# ABC.net
KiCad netlist of a schematic drawn in EAGLE
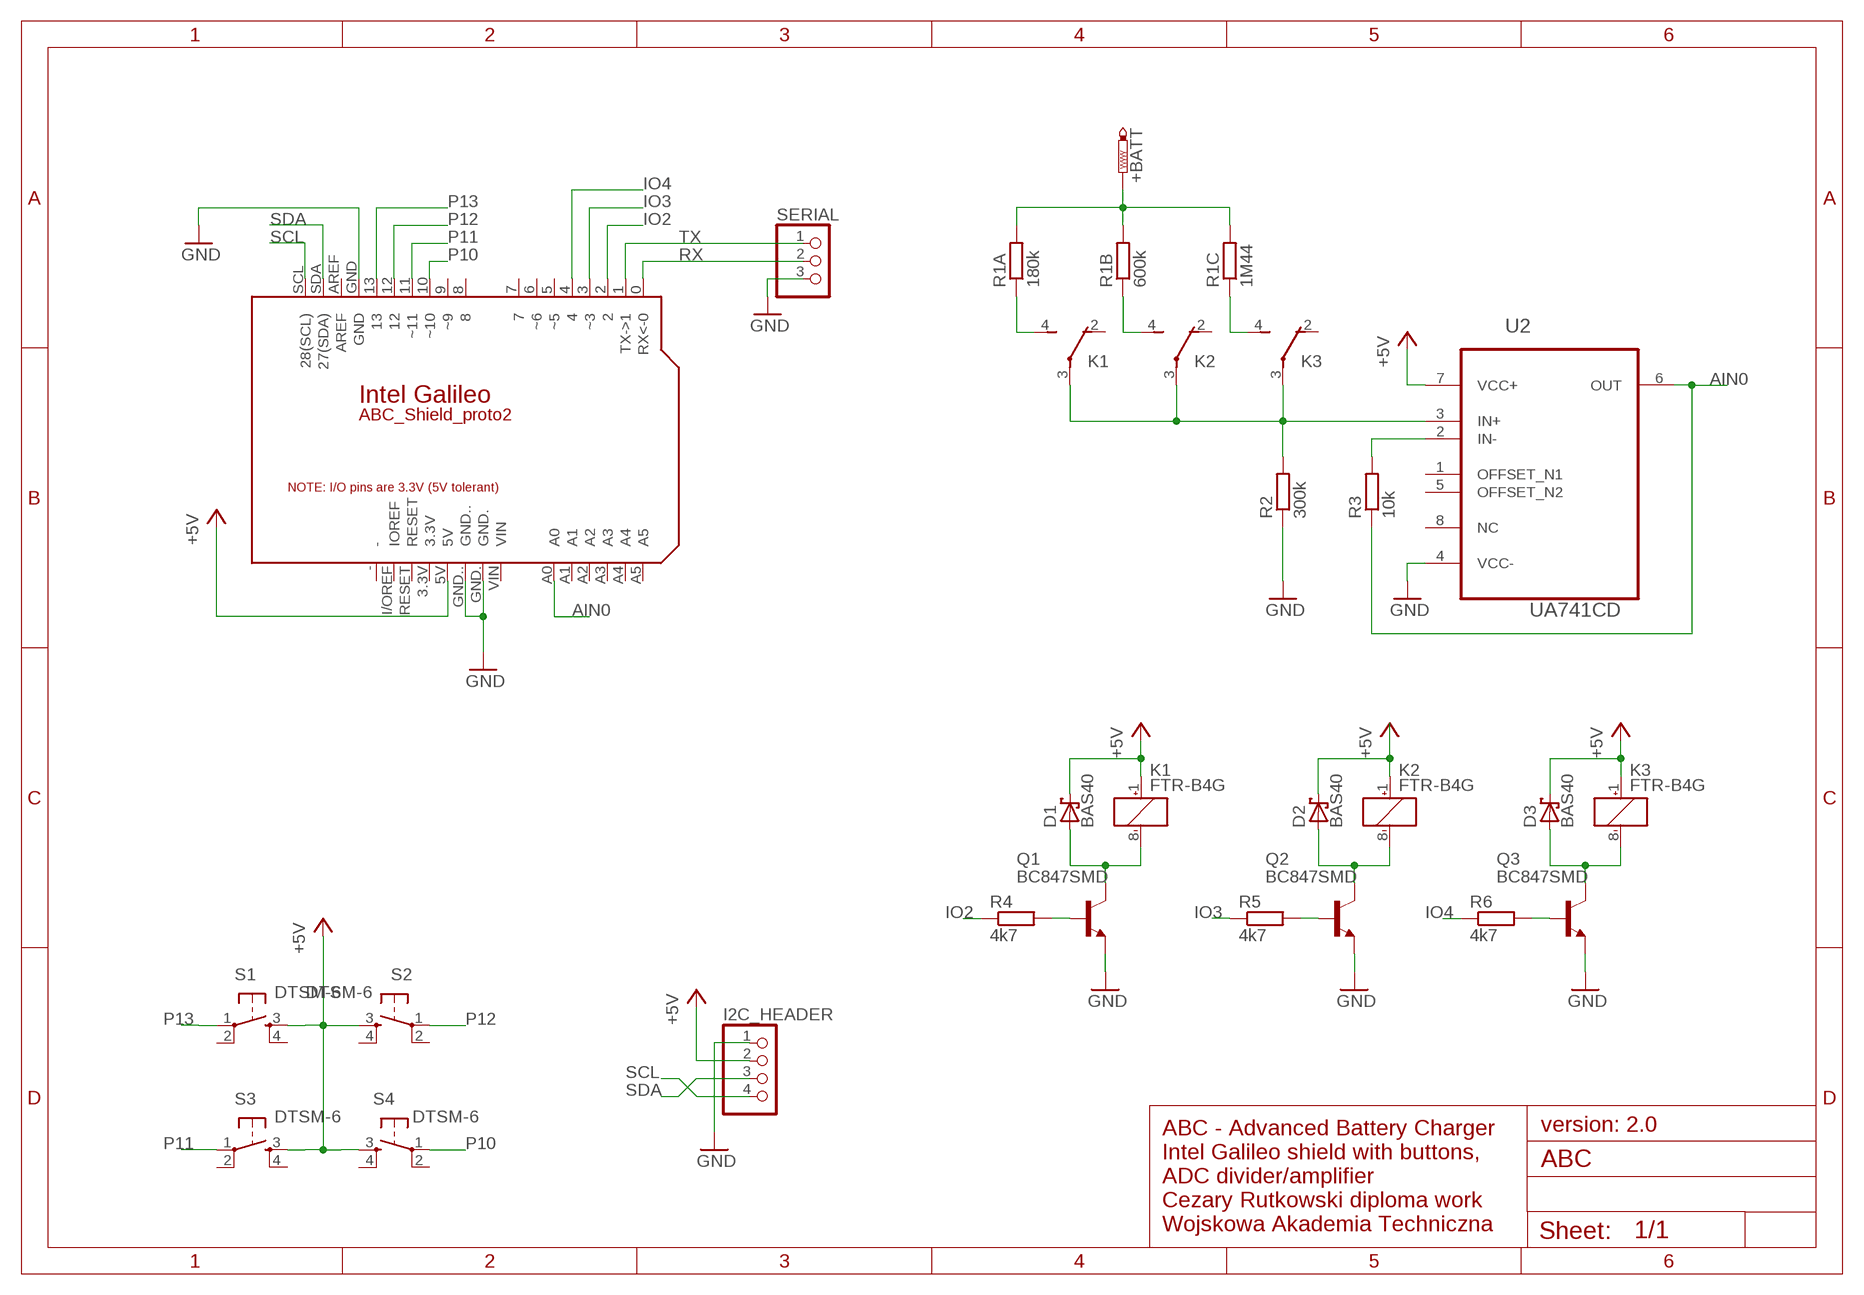
[diagram p0: schematic, sheet 1]

(export (version "E")
  (design (tool "Eeschema 10.0.6"))
  (components
    (comp (ref "+BATT")
      (value "PTR1PAD1-20Y")
      (footprint "eagle-import:P1-20Y")
      (libsource (lib "eagle-import") (part "PTR1PAD1-20Y"))
    )
    (comp (ref "D1")
      (value "BAS40")
      (footprint "eagle-import:SOT23")
      (libsource (lib "eagle-import") (part "BAS40"))
    )
    (comp (ref "D2")
      (value "BAS40")
      (footprint "eagle-import:SOT23")
      (libsource (lib "eagle-import") (part "BAS40"))
    )
    (comp (ref "D3")
      (value "BAS40")
      (footprint "eagle-import:SOT23")
      (libsource (lib "eagle-import") (part "BAS40"))
    )
    (comp (ref "I2C_HEADER")
      (value "PINHD-1X4")
      (footprint "eagle-import:1X04")
      (libsource (lib "eagle-import") (part "PINHD-1X4"))
    )
    (comp (ref "K1")
      (value "FTR-B4G")
      (footprint "eagle-import:FTR-B4G")
      (libsource (lib "eagle-import") (part "FTR-B4G"))
    )
    (comp (ref "K2")
      (value "FTR-B4G")
      (footprint "eagle-import:FTR-B4G")
      (libsource (lib "eagle-import") (part "FTR-B4G"))
    )
    (comp (ref "K3")
      (value "FTR-B4G")
      (footprint "eagle-import:FTR-B4G")
      (libsource (lib "eagle-import") (part "FTR-B4G"))
    )
    (comp (ref "PCB1")
      (value "ARDUINO_101")
      (footprint "eagle-import:ARDUINO_GALILEO")
      (libsource (lib "eagle-import") (part "ARDUINO_101"))
    )
    (comp (ref "Q1")
      (value "BC847SMD")
      (footprint "eagle-import:SOT23")
      (libsource (lib "eagle-import") (part "BC847SMD"))
    )
    (comp (ref "Q2")
      (value "BC847SMD")
      (footprint "eagle-import:SOT23")
      (libsource (lib "eagle-import") (part "BC847SMD"))
    )
    (comp (ref "Q3")
      (value "BC847SMD")
      (footprint "eagle-import:SOT23")
      (libsource (lib "eagle-import") (part "BC847SMD"))
    )
    (comp (ref "R1A")
      (value "180k")
      (footprint "eagle-import:M1206")
      (libsource (lib "eagle-import") (part "R-EU_M1206"))
    )
    (comp (ref "R1B")
      (value "600k")
      (footprint "eagle-import:M1206")
      (libsource (lib "eagle-import") (part "R-EU_M1206"))
    )
    (comp (ref "R1C")
      (value "1M44")
      (footprint "eagle-import:M1206")
      (libsource (lib "eagle-import") (part "R-EU_M1206"))
    )
    (comp (ref "R2")
      (value "300k")
      (footprint "eagle-import:M1206")
      (libsource (lib "eagle-import") (part "R-EU_M1206"))
    )
    (comp (ref "R3")
      (value "10k")
      (footprint "eagle-import:M1206")
      (libsource (lib "eagle-import") (part "R-EU_M1206"))
    )
    (comp (ref "R4")
      (value "4k7")
      (footprint "eagle-import:M1206")
      (libsource (lib "eagle-import") (part "R-EU_M1206"))
    )
    (comp (ref "R5")
      (value "4k7")
      (footprint "eagle-import:M1206")
      (libsource (lib "eagle-import") (part "R-EU_M1206"))
    )
    (comp (ref "R6")
      (value "4k7")
      (footprint "eagle-import:M1206")
      (libsource (lib "eagle-import") (part "R-EU_M1206"))
    )
    (comp (ref "S1")
      (value "DTSM-6")
      (footprint "eagle-import:DTSM-6")
      (libsource (lib "eagle-import") (part "DTSM-6"))
    )
    (comp (ref "S2")
      (value "DTSM-6")
      (footprint "eagle-import:DTSM-6")
      (libsource (lib "eagle-import") (part "DTSM-6"))
    )
    (comp (ref "S3")
      (value "DTSM-6")
      (footprint "eagle-import:DTSM-6")
      (libsource (lib "eagle-import") (part "DTSM-6"))
    )
    (comp (ref "S4")
      (value "DTSM-6")
      (footprint "eagle-import:DTSM-6")
      (libsource (lib "eagle-import") (part "DTSM-6"))
    )
    (comp (ref "SERIAL")
      (value "PINHD-1X3")
      (footprint "eagle-import:1X03")
      (libsource (lib "eagle-import") (part "PINHD-1X3"))
    )
    (comp (ref "U2")
      (value "UA741CD")
      (footprint "eagle-import:SOIC127P600X175-8N")
      (libsource (lib "eagle-import") (part "UA741CD"))
    )
  )
  (nets
    (net (code "1") (name "+5V") (class "Default")
      (node (ref "D1") (pin "3") (pinfunction "C_3") (pintype "passive"))
      (node (ref "D2") (pin "3") (pinfunction "C_3") (pintype "passive"))
      (node (ref "D3") (pin "3") (pinfunction "C_3") (pintype "passive"))
      (node (ref "I2C_HEADER") (pin "2") (pinfunction "2_2") (pintype "passive"))
      (node (ref "K1") (pin "1") (pinfunction "+_1") (pintype "passive"))
      (node (ref "K2") (pin "1") (pinfunction "+_1") (pintype "passive"))
      (node (ref "K3") (pin "1") (pinfunction "+_1") (pintype "passive"))
      (node (ref "PCB1") (pin "5V") (pinfunction "5V_5V") (pintype "bidirectional"))
      (node (ref "S1") (pin "3") (pinfunction "3_3") (pintype "passive"))
      (node (ref "S2") (pin "3") (pinfunction "3_3") (pintype "passive"))
      (node (ref "S3") (pin "3") (pinfunction "3_3") (pintype "passive"))
      (node (ref "S4") (pin "3") (pinfunction "3_3") (pintype "passive"))
      (node (ref "U2") (pin "7") (pinfunction "VCC+_7") (pintype "power_in"))
    )
    (net (code "2") (name "/AIN0") (class "Default")
      (node (ref "PCB1") (pin "A0") (pinfunction "A0_A0") (pintype "bidirectional"))
      (node (ref "R3") (pin "1") (pinfunction "1_1") (pintype "passive"))
      (node (ref "U2") (pin "6") (pinfunction "OUT_6") (pintype "output"))
    )
    (net (code "3") (name "/IO2") (class "Default")
      (node (ref "PCB1") (pin "2") (pinfunction "2_2") (pintype "bidirectional"))
      (node (ref "R4") (pin "1") (pinfunction "1_1") (pintype "passive"))
    )
    (net (code "4") (name "/IO3") (class "Default")
      (node (ref "PCB1") (pin "3") (pinfunction "~{3}_3") (pintype "bidirectional"))
      (node (ref "R5") (pin "1") (pinfunction "1_1") (pintype "passive"))
    )
    (net (code "5") (name "/IO4") (class "Default")
      (node (ref "PCB1") (pin "4") (pinfunction "4_4") (pintype "bidirectional"))
      (node (ref "R6") (pin "1") (pinfunction "1_1") (pintype "passive"))
    )
    (net (code "6") (name "/P10") (class "Default")
      (node (ref "PCB1") (pin "10") (pinfunction "~{10}_10") (pintype "bidirectional"))
      (node (ref "S4") (pin "1") (pinfunction "1_1") (pintype "passive"))
    )
    (net (code "7") (name "/P11") (class "Default")
      (node (ref "PCB1") (pin "11") (pinfunction "~{11}_11") (pintype "bidirectional"))
      (node (ref "S3") (pin "1") (pinfunction "1_1") (pintype "passive"))
    )
    (net (code "8") (name "/P12") (class "Default")
      (node (ref "PCB1") (pin "12") (pinfunction "12_12") (pintype "bidirectional"))
      (node (ref "S2") (pin "1") (pinfunction "1_1") (pintype "passive"))
    )
    (net (code "9") (name "/P13") (class "Default")
      (node (ref "PCB1") (pin "13") (pinfunction "13_13") (pintype "bidirectional"))
      (node (ref "S1") (pin "1") (pinfunction "1_1") (pintype "passive"))
    )
    (net (code "10") (name "/RX") (class "Default")
      (node (ref "PCB1") (pin "0") (pinfunction "RX<-0_0") (pintype "bidirectional"))
      (node (ref "SERIAL") (pin "2") (pinfunction "2_2") (pintype "passive"))
    )
    (net (code "11") (name "/SCL") (class "Default")
      (node (ref "I2C_HEADER") (pin "4") (pinfunction "4_4") (pintype "passive"))
      (node (ref "PCB1") (pin "SCL") (pinfunction "28(SCL)_SCL") (pintype "bidirectional"))
    )
    (net (code "12") (name "/SDA") (class "Default")
      (node (ref "I2C_HEADER") (pin "3") (pinfunction "3_3") (pintype "passive"))
      (node (ref "PCB1") (pin "SDA") (pinfunction "27(SDA)_SDA") (pintype "bidirectional"))
    )
    (net (code "13") (name "/TX") (class "Default")
      (node (ref "PCB1") (pin "1") (pinfunction "TX->1_1") (pintype "bidirectional"))
      (node (ref "SERIAL") (pin "1") (pinfunction "1_1") (pintype "passive"))
    )
    (net (code "14") (name "GND") (class "Default")
      (node (ref "I2C_HEADER") (pin "1") (pinfunction "1_1") (pintype "passive"))
      (node (ref "PCB1") (pin "GND") (pinfunction "GND_GND") (pintype "bidirectional"))
      (node (ref "PCB1") (pin "GND.") (pinfunction "GND._GND.") (pintype "bidirectional"))
      (node (ref "PCB1") (pin "GND..") (pinfunction "GND.._GND..") (pintype "bidirectional"))
      (node (ref "Q1") (pin "2") (pinfunction "E_2") (pintype "passive"))
      (node (ref "Q2") (pin "2") (pinfunction "E_2") (pintype "passive"))
      (node (ref "Q3") (pin "2") (pinfunction "E_2") (pintype "passive"))
      (node (ref "R2") (pin "1") (pinfunction "1_1") (pintype "passive"))
      (node (ref "SERIAL") (pin "3") (pinfunction "3_3") (pintype "passive"))
      (node (ref "U2") (pin "4") (pinfunction "VCC-_4") (pintype "power_in"))
    )
    (net (code "15") (name "Net-(+BATT-PadTP)") (class "Default")
      (node (ref "+BATT") (pin "TP") (pinfunction "TP_TP") (pintype "input"))
      (node (ref "R1A") (pin "2") (pinfunction "2_2") (pintype "passive"))
      (node (ref "R1B") (pin "2") (pinfunction "2_2") (pintype "passive"))
      (node (ref "R1C") (pin "2") (pinfunction "2_2") (pintype "passive"))
    )
    (net (code "16") (name "Net-(D1-A)") (class "Default")
      (node (ref "D1") (pin "1") (pinfunction "A_1") (pintype "passive"))
      (node (ref "K1") (pin "8") (pinfunction "-_8") (pintype "passive"))
      (node (ref "Q1") (pin "3") (pinfunction "C_3") (pintype "passive"))
    )
    (net (code "17") (name "Net-(D2-A)") (class "Default")
      (node (ref "D2") (pin "1") (pinfunction "A_1") (pintype "passive"))
      (node (ref "K2") (pin "8") (pinfunction "-_8") (pintype "passive"))
      (node (ref "Q2") (pin "3") (pinfunction "C_3") (pintype "passive"))
    )
    (net (code "18") (name "Net-(D3-A)") (class "Default")
      (node (ref "D3") (pin "1") (pinfunction "A_1") (pintype "passive"))
      (node (ref "K3") (pin "8") (pinfunction "-_8") (pintype "passive"))
      (node (ref "Q3") (pin "3") (pinfunction "C_3") (pintype "passive"))
    )
    (net (code "19") (name "Net-(K1A-P)") (class "Default")
      (node (ref "K1") (pin "3") (pinfunction "P_3") (pintype "passive"))
      (node (ref "K2") (pin "3") (pinfunction "P_3") (pintype "passive"))
      (node (ref "K3") (pin "3") (pinfunction "P_3") (pintype "passive"))
      (node (ref "R2") (pin "2") (pinfunction "2_2") (pintype "passive"))
      (node (ref "U2") (pin "3") (pinfunction "IN+_3") (pintype "input"))
    )
    (net (code "20") (name "Net-(K1A-S)") (class "Default")
      (node (ref "K1") (pin "4") (pinfunction "S_4") (pintype "passive"))
      (node (ref "R1A") (pin "1") (pinfunction "1_1") (pintype "passive"))
    )
    (net (code "21") (name "Net-(K2A-S)") (class "Default")
      (node (ref "K2") (pin "4") (pinfunction "S_4") (pintype "passive"))
      (node (ref "R1B") (pin "1") (pinfunction "1_1") (pintype "passive"))
    )
    (net (code "22") (name "Net-(K3A-S)") (class "Default")
      (node (ref "K3") (pin "4") (pinfunction "S_4") (pintype "passive"))
      (node (ref "R1C") (pin "1") (pinfunction "1_1") (pintype "passive"))
    )
    (net (code "23") (name "Net-(Q1-B)") (class "Default")
      (node (ref "Q1") (pin "1") (pinfunction "B_1") (pintype "passive"))
      (node (ref "R4") (pin "2") (pinfunction "2_2") (pintype "passive"))
    )
    (net (code "24") (name "Net-(Q2-B)") (class "Default")
      (node (ref "Q2") (pin "1") (pinfunction "B_1") (pintype "passive"))
      (node (ref "R5") (pin "2") (pinfunction "2_2") (pintype "passive"))
    )
    (net (code "25") (name "Net-(Q3-B)") (class "Default")
      (node (ref "Q3") (pin "1") (pinfunction "B_1") (pintype "passive"))
      (node (ref "R6") (pin "2") (pinfunction "2_2") (pintype "passive"))
    )
    (net (code "26") (name "Net-(U2-IN-)") (class "Default")
      (node (ref "R3") (pin "2") (pinfunction "2_2") (pintype "passive"))
      (node (ref "U2") (pin "2") (pinfunction "IN-_2") (pintype "input"))
    )
    (net (code "27") (name "unconnected-(K1A-O-Pad2)") (class "Default")
      (node (ref "K1") (pin "2") (pinfunction "O_2") (pintype "passive"))
    )
    (net (code "28") (name "unconnected-(K2A-O-Pad2)") (class "Default")
      (node (ref "K2") (pin "2") (pinfunction "O_2") (pintype "passive"))
    )
    (net (code "29") (name "unconnected-(K3A-O-Pad2)") (class "Default")
      (node (ref "K3") (pin "2") (pinfunction "O_2") (pintype "passive"))
    )
    (net (code "30") (name "unconnected-(PCB1-IOREF-PadI{slash}OREF)") (class "Default")
      (node (ref "PCB1") (pin "I/OREF") (pinfunction "IOREF_I/OREF") (pintype "bidirectional"))
    )
    (net (code "31") (name "unconnected-(PCB1-Pad-)") (class "Default")
      (node (ref "PCB1") (pin "-") (pinfunction "-_-") (pintype "bidirectional"))
    )
    (net (code "32") (name "unconnected-(PCB1-Pad3.3V)") (class "Default")
      (node (ref "PCB1") (pin "3.3V") (pinfunction "3.3V_3.3V") (pintype "bidirectional"))
    )
    (net (code "33") (name "unconnected-(PCB1-Pad7)") (class "Default")
      (node (ref "PCB1") (pin "7") (pinfunction "7_7") (pintype "bidirectional"))
    )
    (net (code "34") (name "unconnected-(PCB1-Pad8)") (class "Default")
      (node (ref "PCB1") (pin "8") (pinfunction "8_8") (pintype "bidirectional"))
    )
    (net (code "35") (name "unconnected-(PCB1-PadA1)") (class "Default")
      (node (ref "PCB1") (pin "A1") (pinfunction "A1_A1") (pintype "bidirectional"))
    )
    (net (code "36") (name "unconnected-(PCB1-PadA2)") (class "Default")
      (node (ref "PCB1") (pin "A2") (pinfunction "A2_A2") (pintype "bidirectional"))
    )
    (net (code "37") (name "unconnected-(PCB1-PadA3)") (class "Default")
      (node (ref "PCB1") (pin "A3") (pinfunction "A3_A3") (pintype "bidirectional"))
    )
    (net (code "38") (name "unconnected-(PCB1-PadA4)") (class "Default")
      (node (ref "PCB1") (pin "A4") (pinfunction "A4_A4") (pintype "bidirectional"))
    )
    (net (code "39") (name "unconnected-(PCB1-PadA5)") (class "Default")
      (node (ref "PCB1") (pin "A5") (pinfunction "A5_A5") (pintype "bidirectional"))
    )
    (net (code "40") (name "unconnected-(PCB1-PadAREF)") (class "Default")
      (node (ref "PCB1") (pin "AREF") (pinfunction "AREF_AREF") (pintype "bidirectional"))
    )
    (net (code "41") (name "unconnected-(PCB1-PadRESET)") (class "Default")
      (node (ref "PCB1") (pin "RESET") (pinfunction "RESET_RESET") (pintype "bidirectional"))
    )
    (net (code "42") (name "unconnected-(PCB1-PadVIN)") (class "Default")
      (node (ref "PCB1") (pin "VIN") (pinfunction "VIN_VIN") (pintype "bidirectional"))
    )
    (net (code "43") (name "unconnected-(PCB1-~{5}-Pad5)") (class "Default")
      (node (ref "PCB1") (pin "5") (pinfunction "~{5}_5") (pintype "bidirectional"))
    )
    (net (code "44") (name "unconnected-(PCB1-~{6}-Pad6)") (class "Default")
      (node (ref "PCB1") (pin "6") (pinfunction "~{6}_6") (pintype "bidirectional"))
    )
    (net (code "45") (name "unconnected-(PCB1-~{9}-Pad9)") (class "Default")
      (node (ref "PCB1") (pin "9") (pinfunction "~{9}_9") (pintype "bidirectional"))
    )
    (net (code "46") (name "unconnected-(S1-Pad2)") (class "Default")
      (node (ref "S1") (pin "2") (pinfunction "2_2") (pintype "passive"))
    )
    (net (code "47") (name "unconnected-(S1-Pad4)") (class "Default")
      (node (ref "S1") (pin "4") (pinfunction "4_4") (pintype "passive"))
    )
    (net (code "48") (name "unconnected-(S2-Pad2)") (class "Default")
      (node (ref "S2") (pin "2") (pinfunction "2_2") (pintype "passive"))
    )
    (net (code "49") (name "unconnected-(S2-Pad4)") (class "Default")
      (node (ref "S2") (pin "4") (pinfunction "4_4") (pintype "passive"))
    )
    (net (code "50") (name "unconnected-(S3-Pad2)") (class "Default")
      (node (ref "S3") (pin "2") (pinfunction "2_2") (pintype "passive"))
    )
    (net (code "51") (name "unconnected-(S3-Pad4)") (class "Default")
      (node (ref "S3") (pin "4") (pinfunction "4_4") (pintype "passive"))
    )
    (net (code "52") (name "unconnected-(S4-Pad2)") (class "Default")
      (node (ref "S4") (pin "2") (pinfunction "2_2") (pintype "passive"))
    )
    (net (code "53") (name "unconnected-(S4-Pad4)") (class "Default")
      (node (ref "S4") (pin "4") (pinfunction "4_4") (pintype "passive"))
    )
    (net (code "54") (name "unconnected-(U2-NC-Pad8)") (class "Default")
      (node (ref "U2") (pin "8") (pinfunction "NC_8") (pintype "no_connect"))
    )
    (net (code "55") (name "unconnected-(U2-OFFSET_N1-Pad1)") (class "Default")
      (node (ref "U2") (pin "1") (pinfunction "OFFSET_N1_1") (pintype "input"))
    )
    (net (code "56") (name "unconnected-(U2-OFFSET_N2-Pad5)") (class "Default")
      (node (ref "U2") (pin "5") (pinfunction "OFFSET_N2_5") (pintype "input"))
    )
  )
)
